# Mainboard.net
KiCad netlist of a schematic drawn in EAGLE
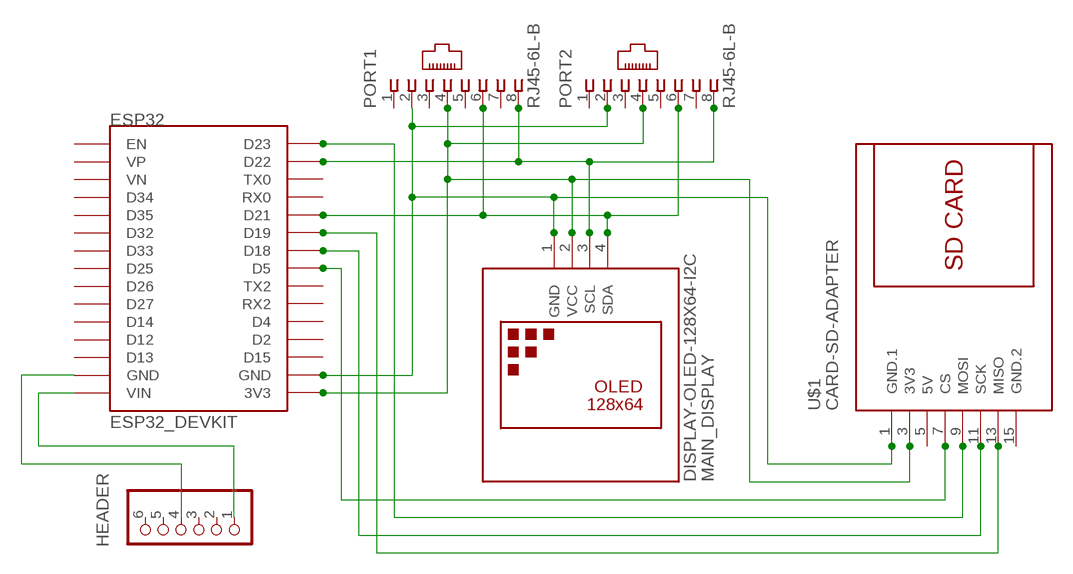
[diagram p0: schematic, sheet 1]

(export (version "E")
  (design (tool "Eeschema 10.0.6"))
  (components
    (comp (ref "ESP32")
      (value "ESP32_DEVKIT")
      (footprint "eagle-import:ESP32_DEVKIT")
      (libsource (lib "eagle-import") (part "ESP32_DEVKIT"))
    )
    (comp (ref "HEADER")
      (value "PINHD-1X6CLEAN")
      (footprint "eagle-import:1X06-CLEAN")
      (libsource (lib "eagle-import") (part "PINHD-1X6CLEAN"))
    )
    (comp (ref "MAIN_DISPLAY")
      (value "DISPLAY-OLED-128X64-I2C")
      (footprint "eagle-import:DISPLAY-OLED-128X64-I2C")
      (libsource (lib "eagle-import") (part "DISPLAY-OLED-128X64-I2C"))
    )
    (comp (ref "PORT1")
      (value "RJ45-6L-B")
      (footprint "eagle-import:RJ45-NO-SHIELD")
      (fields (field (name "SPICEPREFIX") "X"))
      (libsource (lib "eagle-import") (part "RJ45-6L-B"))
    )
    (comp (ref "PORT2")
      (value "RJ45-6L-B")
      (footprint "eagle-import:RJ45-NO-SHIELD")
      (libsource (lib "eagle-import") (part "RJ45-6L-B"))
    )
    (comp (ref "U$1")
      (value "CARD-SD-ADAPTER")
      (footprint "eagle-import:CARD-SD-ADAPTER")
      (libsource (lib "eagle-import") (part "CARD-SD-ADAPTER"))
    )
  )
  (nets
    (net (code "1") (name "/5V") (class "Default")
      (node (ref "U$1") (pin "5") (pinfunction "5V_5") (pintype "power_in"))
    )
    (net (code "2") (name "/GND.2") (class "Default")
      (node (ref "U$1") (pin "15") (pinfunction "GND.2_15") (pintype "power_in"))
    )
    (net (code "3") (name "Net-(ESP32-GND-PadGND@1)") (class "Default")
      (node (ref "ESP32") (pin "GND@1") (pinfunction "GND_GND@1") (pintype "bidirectional"))
      (node (ref "HEADER") (pin "4") (pinfunction "4_4") (pintype "passive"))
    )
    (net (code "4") (name "Net-(ESP32-PadVIN)") (class "Default")
      (node (ref "ESP32") (pin "VIN") (pinfunction "VIN_VIN") (pintype "bidirectional"))
      (node (ref "HEADER") (pin "1") (pinfunction "1_1") (pintype "passive"))
    )
    (net (code "5") (name "Net-(MAIN_DISPLAY-GND)") (class "Default")
      (node (ref "ESP32") (pin "GND@2") (pinfunction "GND_GND@2") (pintype "bidirectional"))
      (node (ref "MAIN_DISPLAY") (pin "1") (pinfunction "GND_1") (pintype "power_in"))
      (node (ref "PORT1") (pin "2") (pinfunction "2_2") (pintype "passive"))
      (node (ref "PORT2") (pin "2") (pinfunction "2_2") (pintype "passive"))
      (node (ref "U$1") (pin "1") (pinfunction "GND.1_1") (pintype "power_in"))
    )
    (net (code "6") (name "Net-(MAIN_DISPLAY-SCL)") (class "Default")
      (node (ref "ESP32") (pin "D22") (pinfunction "D22_D22") (pintype "bidirectional"))
      (node (ref "MAIN_DISPLAY") (pin "3") (pinfunction "SCL_3") (pintype "bidirectional"))
      (node (ref "PORT1") (pin "8") (pinfunction "8_8") (pintype "passive"))
      (node (ref "PORT2") (pin "8") (pinfunction "8_8") (pintype "passive"))
    )
    (net (code "7") (name "Net-(MAIN_DISPLAY-SDA)") (class "Default")
      (node (ref "ESP32") (pin "D21") (pinfunction "D21_D21") (pintype "bidirectional"))
      (node (ref "MAIN_DISPLAY") (pin "4") (pinfunction "SDA_4") (pintype "bidirectional"))
      (node (ref "PORT1") (pin "6") (pinfunction "6_6") (pintype "passive"))
      (node (ref "PORT2") (pin "6") (pinfunction "6_6") (pintype "passive"))
    )
    (net (code "8") (name "Net-(MAIN_DISPLAY-VCC)") (class "Default")
      (node (ref "ESP32") (pin "3V3") (pinfunction "3V3_3V3") (pintype "bidirectional"))
      (node (ref "MAIN_DISPLAY") (pin "2") (pinfunction "VCC_2") (pintype "power_in"))
      (node (ref "PORT1") (pin "4") (pinfunction "4_4") (pintype "passive"))
      (node (ref "PORT2") (pin "4") (pinfunction "4_4") (pintype "passive"))
      (node (ref "U$1") (pin "3") (pinfunction "3V3_3") (pintype "power_in"))
    )
    (net (code "9") (name "Net-(U$1-CS)") (class "Default")
      (node (ref "ESP32") (pin "D5") (pinfunction "D5_D5") (pintype "bidirectional"))
      (node (ref "U$1") (pin "7") (pinfunction "CS_7") (pintype "bidirectional"))
    )
    (net (code "10") (name "Net-(U$1-MISO)") (class "Default")
      (node (ref "ESP32") (pin "D19") (pinfunction "D19_D19") (pintype "bidirectional"))
      (node (ref "U$1") (pin "13") (pinfunction "MISO_13") (pintype "bidirectional"))
    )
    (net (code "11") (name "Net-(U$1-MOSI)") (class "Default")
      (node (ref "ESP32") (pin "D23") (pinfunction "D23_D23") (pintype "bidirectional"))
      (node (ref "U$1") (pin "9") (pinfunction "MOSI_9") (pintype "bidirectional"))
    )
    (net (code "12") (name "Net-(U$1-SCK)") (class "Default")
      (node (ref "ESP32") (pin "D18") (pinfunction "D18_D18") (pintype "bidirectional"))
      (node (ref "U$1") (pin "11") (pinfunction "SCK_11") (pintype "bidirectional"))
    )
    (net (code "13") (name "unconnected-(ESP32-PadD2)") (class "Default")
      (node (ref "ESP32") (pin "D2") (pinfunction "D2_D2") (pintype "bidirectional"))
    )
    (net (code "14") (name "unconnected-(ESP32-PadD4)") (class "Default")
      (node (ref "ESP32") (pin "D4") (pinfunction "D4_D4") (pintype "bidirectional"))
    )
    (net (code "15") (name "unconnected-(ESP32-PadD12)") (class "Default")
      (node (ref "ESP32") (pin "D12") (pinfunction "D12_D12") (pintype "bidirectional"))
    )
    (net (code "16") (name "unconnected-(ESP32-PadD13)") (class "Default")
      (node (ref "ESP32") (pin "D13") (pinfunction "D13_D13") (pintype "bidirectional"))
    )
    (net (code "17") (name "unconnected-(ESP32-PadD14)") (class "Default")
      (node (ref "ESP32") (pin "D14") (pinfunction "D14_D14") (pintype "bidirectional"))
    )
    (net (code "18") (name "unconnected-(ESP32-PadD15)") (class "Default")
      (node (ref "ESP32") (pin "D15") (pinfunction "D15_D15") (pintype "bidirectional"))
    )
    (net (code "19") (name "unconnected-(ESP32-PadD25)") (class "Default")
      (node (ref "ESP32") (pin "D25") (pinfunction "D25_D25") (pintype "bidirectional"))
    )
    (net (code "20") (name "unconnected-(ESP32-PadD26)") (class "Default")
      (node (ref "ESP32") (pin "D26") (pinfunction "D26_D26") (pintype "bidirectional"))
    )
    (net (code "21") (name "unconnected-(ESP32-PadD27)") (class "Default")
      (node (ref "ESP32") (pin "D27") (pinfunction "D27_D27") (pintype "bidirectional"))
    )
    (net (code "22") (name "unconnected-(ESP32-PadD32)") (class "Default")
      (node (ref "ESP32") (pin "D32") (pinfunction "D32_D32") (pintype "bidirectional"))
    )
    (net (code "23") (name "unconnected-(ESP32-PadD33)") (class "Default")
      (node (ref "ESP32") (pin "D33") (pinfunction "D33_D33") (pintype "bidirectional"))
    )
    (net (code "24") (name "unconnected-(ESP32-PadD34)") (class "Default")
      (node (ref "ESP32") (pin "D34") (pinfunction "D34_D34") (pintype "bidirectional"))
    )
    (net (code "25") (name "unconnected-(ESP32-PadD35)") (class "Default")
      (node (ref "ESP32") (pin "D35") (pinfunction "D35_D35") (pintype "bidirectional"))
    )
    (net (code "26") (name "unconnected-(ESP32-PadEN)") (class "Default")
      (node (ref "ESP32") (pin "EN") (pinfunction "EN_EN") (pintype "bidirectional"))
    )
    (net (code "27") (name "unconnected-(ESP32-PadRX0)") (class "Default")
      (node (ref "ESP32") (pin "RX0") (pinfunction "RX0_RX0") (pintype "bidirectional"))
    )
    (net (code "28") (name "unconnected-(ESP32-PadRX2)") (class "Default")
      (node (ref "ESP32") (pin "RX2") (pinfunction "RX2_RX2") (pintype "bidirectional"))
    )
    (net (code "29") (name "unconnected-(ESP32-PadTX0)") (class "Default")
      (node (ref "ESP32") (pin "TX0") (pinfunction "TX0_TX0") (pintype "bidirectional"))
    )
    (net (code "30") (name "unconnected-(ESP32-PadTX2)") (class "Default")
      (node (ref "ESP32") (pin "TX2") (pinfunction "TX2_TX2") (pintype "bidirectional"))
    )
    (net (code "31") (name "unconnected-(ESP32-PadVN)") (class "Default")
      (node (ref "ESP32") (pin "VN") (pinfunction "VN_VN") (pintype "bidirectional"))
    )
    (net (code "32") (name "unconnected-(ESP32-PadVP)") (class "Default")
      (node (ref "ESP32") (pin "VP") (pinfunction "VP_VP") (pintype "bidirectional"))
    )
    (net (code "33") (name "unconnected-(HEADER-Pad2)") (class "Default")
      (node (ref "HEADER") (pin "2") (pinfunction "2_2") (pintype "passive"))
    )
    (net (code "34") (name "unconnected-(HEADER-Pad3)") (class "Default")
      (node (ref "HEADER") (pin "3") (pinfunction "3_3") (pintype "passive"))
    )
    (net (code "35") (name "unconnected-(HEADER-Pad5)") (class "Default")
      (node (ref "HEADER") (pin "5") (pinfunction "5_5") (pintype "passive"))
    )
    (net (code "36") (name "unconnected-(HEADER-Pad6)") (class "Default")
      (node (ref "HEADER") (pin "6") (pinfunction "6_6") (pintype "passive"))
    )
    (net (code "37") (name "unconnected-(PORT1-Pad1)") (class "Default")
      (node (ref "PORT1") (pin "1") (pinfunction "1_1") (pintype "passive"))
    )
    (net (code "38") (name "unconnected-(PORT1-Pad3)") (class "Default")
      (node (ref "PORT1") (pin "3") (pinfunction "3_3") (pintype "passive"))
    )
    (net (code "39") (name "unconnected-(PORT1-Pad5)") (class "Default")
      (node (ref "PORT1") (pin "5") (pinfunction "5_5") (pintype "passive"))
    )
    (net (code "40") (name "unconnected-(PORT1-Pad7)") (class "Default")
      (node (ref "PORT1") (pin "7") (pinfunction "7_7") (pintype "passive"))
    )
    (net (code "41") (name "unconnected-(PORT2-Pad1)") (class "Default")
      (node (ref "PORT2") (pin "1") (pinfunction "1_1") (pintype "passive"))
    )
    (net (code "42") (name "unconnected-(PORT2-Pad3)") (class "Default")
      (node (ref "PORT2") (pin "3") (pinfunction "3_3") (pintype "passive"))
    )
    (net (code "43") (name "unconnected-(PORT2-Pad5)") (class "Default")
      (node (ref "PORT2") (pin "5") (pinfunction "5_5") (pintype "passive"))
    )
    (net (code "44") (name "unconnected-(PORT2-Pad7)") (class "Default")
      (node (ref "PORT2") (pin "7") (pinfunction "7_7") (pintype "passive"))
    )
  )
)
